# sch_CPU.net
KiCad netlist of a schematic drawn in Altium Designer
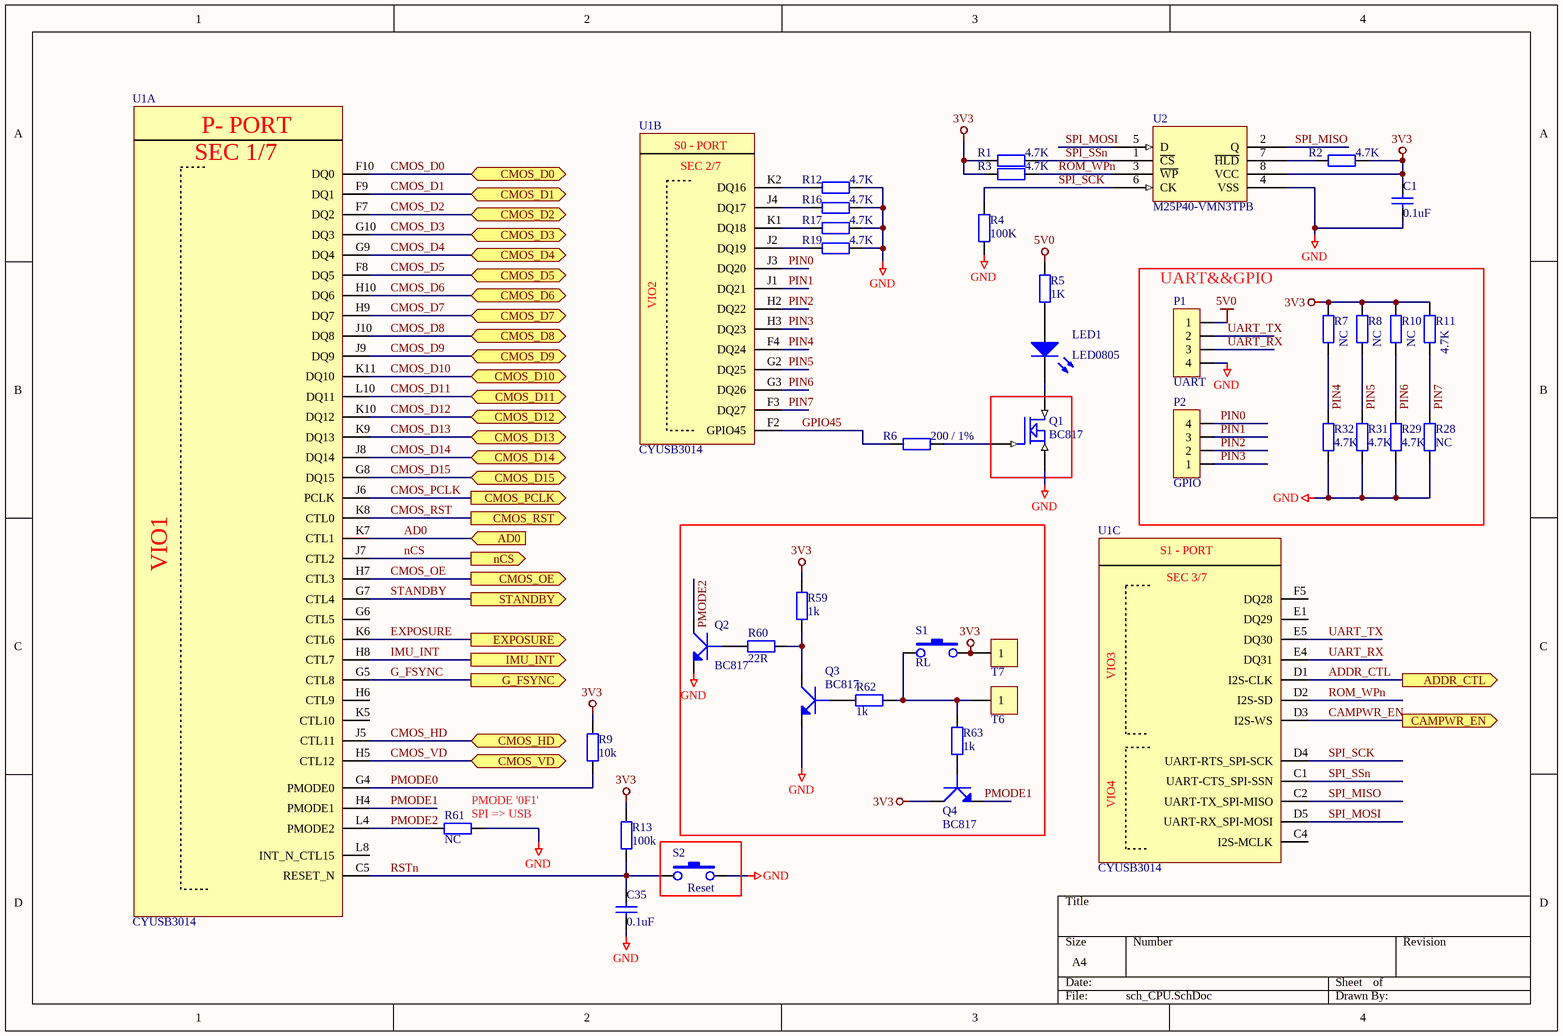
[diagram p0: sch_CPU.SchDoc]

(export (version "E")
  (design (tool "Eeschema 10.0.6"))
  (components
    (comp (ref "C1")
      (value "0.1uF")
      (footprint "0402C")
      (description "Capacitor")
      (fields (field (name "PUBLISHER") "Altium Limited"))
      (libsource (lib "Miscellaneous Devices") (part "Cap"))
    )
    (comp (ref "C35")
      (value "0.1uF")
      (footprint "0402C")
      (description "Capacitor")
      (fields (field (name "PUBLISHER") "Altium Limited"))
      (libsource (lib "Miscellaneous Devices") (part "Cap"))
    )
    (comp (ref "LED1")
      (value "LED0805")
      (footprint "LED0805A_L210W100H60")
      (description "发光二级管")
      (libsource (lib "TXW") (part "LED"))
    )
    (comp (ref "P1")
      (value "UART")
      (footprint "WAFER4_P1.25L6.25W3.4H4.3")
      (libsource (lib "KS_Drive") (part "CON4"))
    )
    (comp (ref "P2")
      (value "GPIO")
      (footprint "WAFER4_P1.25L6.25W3.4H4.3")
      (libsource (lib "") (part "CON4_1"))
    )
    (comp (ref "Q1")
      (value "BC817")
      (footprint "SOT-23L")
      (description "MOSFET N")
      (libsource (lib "TXW") (part "MOSFET N"))
    )
    (comp (ref "Q2")
      (value "BC817")
      (footprint "SOT-23L")
      (description "NPN Transistor")
      (libsource (lib "*") (part "NPN"))
    )
    (comp (ref "Q3")
      (value "BC817")
      (footprint "SOT-23L")
      (description "NPN Transistor")
      (libsource (lib "*") (part "NPN"))
    )
    (comp (ref "Q4")
      (value "BC817")
      (footprint "SOT-23L")
      (description "NPN Transistor")
      (libsource (lib "") (part "NPN_1"))
    )
    (comp (ref "R1")
      (value "4.7K")
      (footprint "0402R")
      (description "Resistor")
      (fields (field (name "PUBLISHER") "Altium Limited"))
      (libsource (lib "SZG") (part "Resistor"))
    )
    (comp (ref "R2")
      (value "4.7K")
      (footprint "0402R")
      (description "Resistor")
      (fields (field (name "PUBLISHER") "Altium Limited"))
      (libsource (lib "SZG") (part "Resistor"))
    )
    (comp (ref "R3")
      (value "4.7K")
      (footprint "0402R")
      (description "Resistor")
      (fields (field (name "PUBLISHER") "Altium Limited"))
      (libsource (lib "SZG") (part "Resistor"))
    )
    (comp (ref "R4")
      (value "100K")
      (footprint "0402R")
      (description "Resistor")
      (fields (field (name "PUBLISHER") "Altium Limited"))
      (libsource (lib "") (part "Resistor_1"))
    )
    (comp (ref "R5")
      (value "1K")
      (footprint "0402R")
      (description "Resistor")
      (fields (field (name "PUBLISHER") "Altium Limited"))
      (libsource (lib "") (part "Resistor_2"))
    )
    (comp (ref "R6")
      (value "200 / 1%")
      (footprint "0402R")
      (description "Resistor")
      (fields (field (name "Comment") "200R") (field (name "PUBLISHER") "Altium Limited"))
      (libsource (lib "SZG") (part "Resistor"))
    )
    (comp (ref "R7")
      (value "NC")
      (footprint "0402R")
      (description "Resistor")
      (fields (field (name "Comment") "4.7K") (field (name "PUBLISHER") "Altium Limited"))
      (libsource (lib "") (part "Resistor_1"))
    )
    (comp (ref "R8")
      (value "NC")
      (footprint "0402R")
      (description "Resistor")
      (fields (field (name "Comment") "4.7K") (field (name "PUBLISHER") "Altium Limited"))
      (libsource (lib "") (part "Resistor_1"))
    )
    (comp (ref "R9")
      (value "10k")
      (footprint "0402R")
      (description "Resistor")
      (fields (field (name "Comment") "10K") (field (name "PUBLISHER") "Altium Limited"))
      (libsource (lib "") (part "Resistor_2"))
    )
    (comp (ref "R10")
      (value "NC")
      (footprint "0402R")
      (description "Resistor")
      (fields (field (name "Comment") "4.7K") (field (name "PUBLISHER") "Altium Limited"))
      (libsource (lib "") (part "Resistor_1"))
    )
    (comp (ref "R11")
      (value "4.7K")
      (footprint "0402R")
      (description "Resistor")
      (fields (field (name "PUBLISHER") "Altium Limited"))
      (libsource (lib "") (part "Resistor_1"))
    )
    (comp (ref "R12")
      (value "4.7K")
      (footprint "0402R")
      (description "Resistor")
      (fields (field (name "PUBLISHER") "Altium Limited"))
      (libsource (lib "SZG") (part "Resistor"))
    )
    (comp (ref "R13")
      (value "100k")
      (footprint "0402R")
      (description "Resistor")
      (fields (field (name "Comment") "100K") (field (name "PUBLISHER") "Altium Limited"))
      (libsource (lib "") (part "Resistor_2"))
    )
    (comp (ref "R16")
      (value "4.7K")
      (footprint "0402R")
      (description "Resistor")
      (fields (field (name "PUBLISHER") "Altium Limited"))
      (libsource (lib "SZG") (part "Resistor"))
    )
    (comp (ref "R17")
      (value "4.7K")
      (footprint "0402R")
      (description "Resistor")
      (fields (field (name "PUBLISHER") "Altium Limited"))
      (libsource (lib "SZG") (part "Resistor"))
    )
    (comp (ref "R19")
      (value "4.7K")
      (footprint "0402R")
      (description "Resistor")
      (fields (field (name "PUBLISHER") "Altium Limited"))
      (libsource (lib "SZG") (part "Resistor"))
    )
    (comp (ref "R28")
      (value "NC")
      (footprint "0402R")
      (description "Resistor")
      (fields (field (name "Comment") "4.7K") (field (name "PUBLISHER") "Altium Limited"))
      (libsource (lib "") (part "Resistor_2"))
    )
    (comp (ref "R29")
      (value "4.7K")
      (footprint "0402R")
      (description "Resistor")
      (fields (field (name "PUBLISHER") "Altium Limited"))
      (libsource (lib "") (part "Resistor_2"))
    )
    (comp (ref "R31")
      (value "4.7K")
      (footprint "0402R")
      (description "Resistor")
      (fields (field (name "PUBLISHER") "Altium Limited"))
      (libsource (lib "") (part "Resistor_2"))
    )
    (comp (ref "R32")
      (value "4.7K")
      (footprint "0402R")
      (description "Resistor")
      (fields (field (name "PUBLISHER") "Altium Limited"))
      (libsource (lib "") (part "Resistor_2"))
    )
    (comp (ref "R59")
      (value "1k")
      (footprint "0402R")
      (description "Resistor")
      (fields (field (name "Comment") "1K") (field (name "PUBLISHER") "Altium Limited"))
      (libsource (lib "") (part "Resistor_1"))
    )
    (comp (ref "R60")
      (value "22R")
      (footprint "0402R")
      (description "Resistor")
      (fields (field (name "PUBLISHER") "Altium Limited"))
      (libsource (lib "SZG") (part "Resistor"))
    )
    (comp (ref "R61")
      (value "NC")
      (footprint "0805R")
      (description "Resistor")
      (fields (field (name "PUBLISHER") "Altium Limited"))
      (libsource (lib "") (part "Resistor_3"))
    )
    (comp (ref "R62")
      (value "1k")
      (footprint "0402R")
      (description "Resistor")
      (fields (field (name "PUBLISHER") "Altium Limited"))
      (libsource (lib "") (part "Resistor_3"))
    )
    (comp (ref "R63")
      (value "1k")
      (footprint "0402R")
      (description "Resistor")
      (fields (field (name "PUBLISHER") "Altium Limited"))
      (libsource (lib "") (part "Resistor_2"))
    )
    (comp (ref "S1")
      (value "RL")
      (footprint "SW_L40W30H25_MPTFP")
      (description "Button_sop")
      (libsource (lib "SZG") (part "Button_sop"))
    )
    (comp (ref "S2")
      (value "Reset")
      (footprint "SW_L40W30H25_MPTFP")
      (description "Button_sop")
      (libsource (lib "SZG") (part "Button_sop"))
    )
    (comp (ref "T6")
      (value "CON1")
      (footprint "PAD_TP_D1.2")
      (description "Connector")
      (libsource (lib "SuperSchLib") (part "CON1"))
    )
    (comp (ref "T7")
      (value "CON1")
      (footprint "PAD_TP_D1.2")
      (description "Connector")
      (libsource (lib "SuperSchLib") (part "CON1"))
    )
    (comp (ref "U1")
      (value "CYUSB3014")
      (footprint "FBGA121_P80L100W100H11")
      (libsource (lib "TXW") (part "CYUSB3014"))
    )
    (comp (ref "U2")
      (value "M25P40-VMN3TPB")
      (footprint "SO8N_P127L50W40W62H17")
      (libsource (lib "TXW") (part "M25P40-VMN3TPB"))
    )
  )
  (nets
    (net (code "1") (name "/AD0") (class "Default")
      (node (ref "U1") (pin "K7") (pinfunction "CTL1_K7") (pintype "passive"))
    )
    (net (code "2") (name "/ADDR_CTL") (class "Default")
      (node (ref "U1") (pin "D1") (pinfunction "I2S-CLK_D1") (pintype "passive"))
    )
    (net (code "3") (name "/CAMPWR_EN") (class "Default")
      (node (ref "U1") (pin "D3") (pinfunction "I2S-WS_D3") (pintype "passive"))
    )
    (net (code "4") (name "/CMOS_D0") (class "Default")
      (node (ref "U1") (pin "F10") (pinfunction "DQ0_F10") (pintype "passive"))
    )
    (net (code "5") (name "/CMOS_D1") (class "Default")
      (node (ref "U1") (pin "F9") (pinfunction "DQ1_F9") (pintype "passive"))
    )
    (net (code "6") (name "/CMOS_D2") (class "Default")
      (node (ref "U1") (pin "F7") (pinfunction "DQ2_F7") (pintype "passive"))
    )
    (net (code "7") (name "/CMOS_D3") (class "Default")
      (node (ref "U1") (pin "G10") (pinfunction "DQ3_G10") (pintype "passive"))
    )
    (net (code "8") (name "/CMOS_D4") (class "Default")
      (node (ref "U1") (pin "G9") (pinfunction "DQ4_G9") (pintype "passive"))
    )
    (net (code "9") (name "/CMOS_D5") (class "Default")
      (node (ref "U1") (pin "F8") (pinfunction "DQ5_F8") (pintype "passive"))
    )
    (net (code "10") (name "/CMOS_D6") (class "Default")
      (node (ref "U1") (pin "H10") (pinfunction "DQ6_H10") (pintype "passive"))
    )
    (net (code "11") (name "/CMOS_D7") (class "Default")
      (node (ref "U1") (pin "H9") (pinfunction "DQ7_H9") (pintype "passive"))
    )
    (net (code "12") (name "/CMOS_D8") (class "Default")
      (node (ref "U1") (pin "J10") (pinfunction "DQ8_J10") (pintype "passive"))
    )
    (net (code "13") (name "/CMOS_D9") (class "Default")
      (node (ref "U1") (pin "J9") (pinfunction "DQ9_J9") (pintype "passive"))
    )
    (net (code "14") (name "/CMOS_D10") (class "Default")
      (node (ref "U1") (pin "K11") (pinfunction "DQ10_K11") (pintype "passive"))
    )
    (net (code "15") (name "/CMOS_D11") (class "Default")
      (node (ref "U1") (pin "L10") (pinfunction "DQ11_L10") (pintype "passive"))
    )
    (net (code "16") (name "/CMOS_D12") (class "Default")
      (node (ref "U1") (pin "K10") (pinfunction "DQ12_K10") (pintype "passive"))
    )
    (net (code "17") (name "/CMOS_D13") (class "Default")
      (node (ref "U1") (pin "K9") (pinfunction "DQ13_K9") (pintype "passive"))
    )
    (net (code "18") (name "/CMOS_D14") (class "Default")
      (node (ref "U1") (pin "J8") (pinfunction "DQ14_J8") (pintype "passive"))
    )
    (net (code "19") (name "/CMOS_D15") (class "Default")
      (node (ref "U1") (pin "G8") (pinfunction "DQ15_G8") (pintype "passive"))
    )
    (net (code "20") (name "/CMOS_HD") (class "Default")
      (node (ref "U1") (pin "J5") (pinfunction "CTL11_J5") (pintype "passive"))
    )
    (net (code "21") (name "/CMOS_OE") (class "Default")
      (node (ref "U1") (pin "H7") (pinfunction "CTL3_H7") (pintype "passive"))
    )
    (net (code "22") (name "/CMOS_PCLK") (class "Default")
      (node (ref "U1") (pin "J6") (pinfunction "PCLK_J6") (pintype "passive"))
    )
    (net (code "23") (name "/CMOS_RST") (class "Default")
      (node (ref "U1") (pin "K8") (pinfunction "CTL0_K8") (pintype "passive"))
    )
    (net (code "24") (name "/CMOS_VD") (class "Default")
      (node (ref "U1") (pin "H5") (pinfunction "CTL12_H5") (pintype "passive"))
    )
    (net (code "25") (name "/EXPOSURE") (class "Default")
      (node (ref "U1") (pin "K6") (pinfunction "CTL6_K6") (pintype "passive"))
    )
    (net (code "26") (name "/GPIO45") (class "Default")
      (node (ref "R6") (pin "1") (pinfunction "1_1") (pintype "passive"))
      (node (ref "U1") (pin "F2") (pinfunction "GPIO45_F2") (pintype "passive"))
    )
    (net (code "27") (name "/G_FSYNC") (class "Default")
      (node (ref "U1") (pin "G5") (pinfunction "CTL8_G5") (pintype "passive"))
    )
    (net (code "28") (name "/IMU_INT") (class "Default")
      (node (ref "U1") (pin "H8") (pinfunction "CTL7_H8") (pintype "passive"))
    )
    (net (code "29") (name "/PIN0") (class "Default")
      (node (ref "P2") (pin "4") (pinfunction "4_4") (pintype "passive"))
      (node (ref "U1") (pin "J3") (pinfunction "DQ20_J3") (pintype "passive"))
    )
    (net (code "30") (name "/PIN1") (class "Default")
      (node (ref "P2") (pin "3") (pinfunction "3_3") (pintype "passive"))
      (node (ref "U1") (pin "J1") (pinfunction "DQ21_J1") (pintype "passive"))
    )
    (net (code "31") (name "/PIN2") (class "Default")
      (node (ref "P2") (pin "2") (pinfunction "2_2") (pintype "passive"))
      (node (ref "U1") (pin "H2") (pinfunction "DQ22_H2") (pintype "passive"))
    )
    (net (code "32") (name "/PIN3") (class "Default")
      (node (ref "P2") (pin "1") (pinfunction "1_1") (pintype "passive"))
      (node (ref "U1") (pin "H3") (pinfunction "DQ23_H3") (pintype "passive"))
    )
    (net (code "33") (name "/PIN4") (class "Default")
      (node (ref "R32") (pin "1") (pinfunction "1_1") (pintype "passive"))
      (node (ref "R7") (pin "1") (pinfunction "1_1") (pintype "passive"))
      (node (ref "U1") (pin "F4") (pinfunction "DQ24_F4") (pintype "passive"))
    )
    (net (code "34") (name "/PIN5") (class "Default")
      (node (ref "R31") (pin "1") (pinfunction "1_1") (pintype "passive"))
      (node (ref "R8") (pin "1") (pinfunction "1_1") (pintype "passive"))
      (node (ref "U1") (pin "G2") (pinfunction "DQ25_G2") (pintype "passive"))
    )
    (net (code "35") (name "/PIN6") (class "Default")
      (node (ref "R10") (pin "1") (pinfunction "1_1") (pintype "passive"))
      (node (ref "R29") (pin "1") (pinfunction "1_1") (pintype "passive"))
      (node (ref "U1") (pin "G3") (pinfunction "DQ26_G3") (pintype "passive"))
    )
    (net (code "36") (name "/PIN7") (class "Default")
      (node (ref "R11") (pin "1") (pinfunction "1_1") (pintype "passive"))
      (node (ref "R28") (pin "1") (pinfunction "1_1") (pintype "passive"))
      (node (ref "U1") (pin "F3") (pinfunction "DQ27_F3") (pintype "passive"))
    )
    (net (code "37") (name "/PMODE0") (class "Default")
      (node (ref "R9") (pin "2") (pinfunction "2_2") (pintype "passive"))
      (node (ref "U1") (pin "G4") (pinfunction "PMODE0_G4") (pintype "passive"))
    )
    (net (code "38") (name "/PMODE1") (class "Default")
      (node (ref "Q4") (pin "2") (pinfunction "E_2") (pintype "passive"))
      (node (ref "U1") (pin "H4") (pinfunction "PMODE1_H4") (pintype "passive"))
    )
    (net (code "39") (name "/PMODE2") (class "Default")
      (node (ref "Q2") (pin "3") (pinfunction "C_3") (pintype "passive"))
      (node (ref "R61") (pin "2") (pinfunction "2_2") (pintype "passive"))
      (node (ref "U1") (pin "L4") (pinfunction "PMODE2_L4") (pintype "passive"))
    )
    (net (code "40") (name "/ROM_WPn") (class "Default")
      (node (ref "R3") (pin "2") (pinfunction "2_2") (pintype "passive"))
      (node (ref "U1") (pin "D2") (pinfunction "I2S-SD_D2") (pintype "passive"))
      (node (ref "U2") (pin "3") (pinfunction "~{WP}_3") (pintype "passive"))
    )
    (net (code "41") (name "/RSTn") (class "Default")
      (node (ref "C35") (pin "2") (pinfunction "2_2") (pintype "passive"))
      (node (ref "R13") (pin "2") (pinfunction "2_2") (pintype "passive"))
      (node (ref "S2") (pin "1") (pinfunction "1_1") (pintype "passive"))
      (node (ref "U1") (pin "C5") (pinfunction "RESET_N_C5") (pintype "passive"))
    )
    (net (code "42") (name "/SPI_MISO") (class "Default")
      (node (ref "U1") (pin "C2") (pinfunction "UART-TX_SPI-MISO_C2") (pintype "passive"))
      (node (ref "U2") (pin "2") (pinfunction "Q_2") (pintype "passive"))
    )
    (net (code "43") (name "/SPI_MOSI") (class "Default")
      (node (ref "U1") (pin "D5") (pinfunction "UART-RX_SPI-MOSI_D5") (pintype "passive"))
      (node (ref "U2") (pin "5") (pinfunction "D_5") (pintype "input"))
    )
    (net (code "44") (name "/SPI_SCK") (class "Default")
      (node (ref "R4") (pin "2") (pinfunction "2_2") (pintype "passive"))
      (node (ref "U1") (pin "D4") (pinfunction "UART-RTS_SPI-SCK_D4") (pintype "passive"))
      (node (ref "U2") (pin "6") (pinfunction "CK_6") (pintype "input"))
    )
    (net (code "45") (name "/SPI_SSn") (class "Default")
      (node (ref "R1") (pin "2") (pinfunction "2_2") (pintype "passive"))
      (node (ref "U1") (pin "C1") (pinfunction "UART-CTS_SPI-SSN_C1") (pintype "passive"))
      (node (ref "U2") (pin "1") (pinfunction "~{CS}_1") (pintype "passive"))
    )
    (net (code "46") (name "/STANDBY") (class "Default")
      (node (ref "U1") (pin "G7") (pinfunction "CTL4_G7") (pintype "passive"))
    )
    (net (code "47") (name "/UART_RX") (class "Default")
      (node (ref "P1") (pin "3") (pinfunction "3_3") (pintype "passive"))
      (node (ref "U1") (pin "E4") (pinfunction "DQ31_E4") (pintype "passive"))
    )
    (net (code "48") (name "/UART_TX") (class "Default")
      (node (ref "P1") (pin "2") (pinfunction "2_2") (pintype "passive"))
      (node (ref "U1") (pin "E5") (pinfunction "DQ30_E5") (pintype "passive"))
    )
    (net (code "49") (name "/nCS") (class "Default")
      (node (ref "U1") (pin "J7") (pinfunction "CTL2_J7") (pintype "passive"))
    )
    (net (code "50") (name "3V3") (class "Default")
      (node (ref "C1") (pin "2") (pinfunction "2_2") (pintype "passive"))
      (node (ref "Q4") (pin "3") (pinfunction "C_3") (pintype "passive"))
      (node (ref "R1") (pin "1") (pinfunction "1_1") (pintype "passive"))
      (node (ref "R10") (pin "2") (pinfunction "2_2") (pintype "passive"))
      (node (ref "R11") (pin "2") (pinfunction "2_2") (pintype "passive"))
      (node (ref "R13") (pin "1") (pinfunction "1_1") (pintype "passive"))
      (node (ref "R2") (pin "2") (pinfunction "2_2") (pintype "passive"))
      (node (ref "R3") (pin "1") (pinfunction "1_1") (pintype "passive"))
      (node (ref "R59") (pin "2") (pinfunction "2_2") (pintype "passive"))
      (node (ref "R7") (pin "2") (pinfunction "2_2") (pintype "passive"))
      (node (ref "R8") (pin "2") (pinfunction "2_2") (pintype "passive"))
      (node (ref "R9") (pin "1") (pinfunction "1_1") (pintype "passive"))
      (node (ref "S1") (pin "1") (pinfunction "1_1") (pintype "passive"))
      (node (ref "T7") (pin "1") (pinfunction "1_1") (pintype "passive"))
      (node (ref "U2") (pin "8") (pinfunction "VCC_8") (pintype "passive"))
    )
    (net (code "51") (name "5V0") (class "Default")
      (node (ref "P1") (pin "1") (pinfunction "1_1") (pintype "passive"))
      (node (ref "R5") (pin "1") (pinfunction "1_1") (pintype "passive"))
    )
    (net (code "52") (name "GND") (class "Default")
      (node (ref "C1") (pin "1") (pinfunction "1_1") (pintype "passive"))
      (node (ref "C35") (pin "1") (pinfunction "1_1") (pintype "passive"))
      (node (ref "P1") (pin "4") (pinfunction "4_4") (pintype "passive"))
      (node (ref "Q1") (pin "2") (pinfunction "S_2") (pintype "input"))
      (node (ref "Q2") (pin "2") (pinfunction "E_2") (pintype "passive"))
      (node (ref "Q3") (pin "2") (pinfunction "E_2") (pintype "passive"))
      (node (ref "R12") (pin "2") (pinfunction "2_2") (pintype "passive"))
      (node (ref "R16") (pin "2") (pinfunction "2_2") (pintype "passive"))
      (node (ref "R17") (pin "2") (pinfunction "2_2") (pintype "passive"))
      (node (ref "R19") (pin "2") (pinfunction "2_2") (pintype "passive"))
      (node (ref "R28") (pin "2") (pinfunction "2_2") (pintype "passive"))
      (node (ref "R29") (pin "2") (pinfunction "2_2") (pintype "passive"))
      (node (ref "R31") (pin "2") (pinfunction "2_2") (pintype "passive"))
      (node (ref "R32") (pin "2") (pinfunction "2_2") (pintype "passive"))
      (node (ref "R4") (pin "1") (pinfunction "1_1") (pintype "passive"))
      (node (ref "R61") (pin "1") (pinfunction "1_1") (pintype "passive"))
      (node (ref "S2") (pin "2") (pinfunction "2_2") (pintype "passive"))
      (node (ref "U2") (pin "4") (pinfunction "VSS_4") (pintype "passive"))
    )
    (net (code "53") (name "Net-(LED1-A)") (class "Default")
      (node (ref "LED1") (pin "1") (pinfunction "A_1") (pintype "passive"))
      (node (ref "R5") (pin "2") (pinfunction "2_2") (pintype "passive"))
    )
    (net (code "54") (name "Net-(LED1-K)") (class "Default")
      (node (ref "LED1") (pin "2") (pinfunction "K_2") (pintype "passive"))
      (node (ref "Q1") (pin "3") (pinfunction "D_3") (pintype "input"))
    )
    (net (code "55") (name "Net-(Q1-G)") (class "Default")
      (node (ref "Q1") (pin "1") (pinfunction "G_1") (pintype "input"))
      (node (ref "R6") (pin "2") (pinfunction "2_2") (pintype "passive"))
    )
    (net (code "56") (name "Net-(Q2-B)") (class "Default")
      (node (ref "Q2") (pin "1") (pinfunction "B_1") (pintype "passive"))
      (node (ref "R60") (pin "1") (pinfunction "1_1") (pintype "passive"))
    )
    (net (code "57") (name "Net-(Q3-B)") (class "Default")
      (node (ref "Q3") (pin "1") (pinfunction "B_1") (pintype "passive"))
      (node (ref "R62") (pin "2") (pinfunction "2_2") (pintype "passive"))
    )
    (net (code "58") (name "Net-(Q3-C)") (class "Default")
      (node (ref "Q3") (pin "3") (pinfunction "C_3") (pintype "passive"))
      (node (ref "R59") (pin "1") (pinfunction "1_1") (pintype "passive"))
      (node (ref "R60") (pin "2") (pinfunction "2_2") (pintype "passive"))
    )
    (net (code "59") (name "Net-(Q4-B)") (class "Default")
      (node (ref "Q4") (pin "1") (pinfunction "B_1") (pintype "passive"))
      (node (ref "R63") (pin "2") (pinfunction "2_2") (pintype "passive"))
    )
    (net (code "60") (name "Net-(R62-Pad1)") (class "Default")
      (node (ref "R62") (pin "1") (pinfunction "1_1") (pintype "passive"))
      (node (ref "R63") (pin "1") (pinfunction "1_1") (pintype "passive"))
      (node (ref "S1") (pin "2") (pinfunction "2_2") (pintype "passive"))
      (node (ref "T6") (pin "1") (pinfunction "1_1") (pintype "passive"))
    )
    (net (code "61") (name "Net-(U1B-DQ16)") (class "Default")
      (node (ref "R12") (pin "1") (pinfunction "1_1") (pintype "passive"))
      (node (ref "U1") (pin "K2") (pinfunction "DQ16_K2") (pintype "passive"))
    )
    (net (code "62") (name "Net-(U1B-DQ17)") (class "Default")
      (node (ref "R16") (pin "1") (pinfunction "1_1") (pintype "passive"))
      (node (ref "U1") (pin "J4") (pinfunction "DQ17_J4") (pintype "passive"))
    )
    (net (code "63") (name "Net-(U1B-DQ18)") (class "Default")
      (node (ref "R17") (pin "1") (pinfunction "1_1") (pintype "passive"))
      (node (ref "U1") (pin "K1") (pinfunction "DQ18_K1") (pintype "passive"))
    )
    (net (code "64") (name "Net-(U1B-DQ19)") (class "Default")
      (node (ref "R19") (pin "1") (pinfunction "1_1") (pintype "passive"))
      (node (ref "U1") (pin "J2") (pinfunction "DQ19_J2") (pintype "passive"))
    )
    (net (code "65") (name "Net-(U2-~{HLD})") (class "Default")
      (node (ref "R2") (pin "1") (pinfunction "1_1") (pintype "passive"))
      (node (ref "U2") (pin "7") (pinfunction "~{HLD}_7") (pintype "passive"))
    )
    (net (code "66") (name "unconnected-(U1A-CTL5-PadG6)") (class "Default")
      (node (ref "U1") (pin "G6") (pinfunction "CTL5_G6") (pintype "passive"))
    )
    (net (code "67") (name "unconnected-(U1A-CTL9-PadH6)") (class "Default")
      (node (ref "U1") (pin "H6") (pinfunction "CTL9_H6") (pintype "passive"))
    )
    (net (code "68") (name "unconnected-(U1A-CTL10-PadK5)") (class "Default")
      (node (ref "U1") (pin "K5") (pinfunction "CTL10_K5") (pintype "passive"))
    )
    (net (code "69") (name "unconnected-(U1A-INT_N_CTL15-PadL8)") (class "Default")
      (node (ref "U1") (pin "L8") (pinfunction "INT_N_CTL15_L8") (pintype "passive"))
    )
    (net (code "70") (name "unconnected-(U1C-DQ28-PadF5)") (class "Default")
      (node (ref "U1") (pin "F5") (pinfunction "DQ28_F5") (pintype "passive"))
    )
    (net (code "71") (name "unconnected-(U1C-DQ29-PadE1)") (class "Default")
      (node (ref "U1") (pin "E1") (pinfunction "DQ29_E1") (pintype "passive"))
    )
    (net (code "72") (name "unconnected-(U1C-I2S-MCLK-PadC4)") (class "Default")
      (node (ref "U1") (pin "C4") (pinfunction "I2S-MCLK_C4") (pintype "passive"))
    )
  )
)
